# metrowing.net
KiCad netlist of a schematic drawn in EAGLE
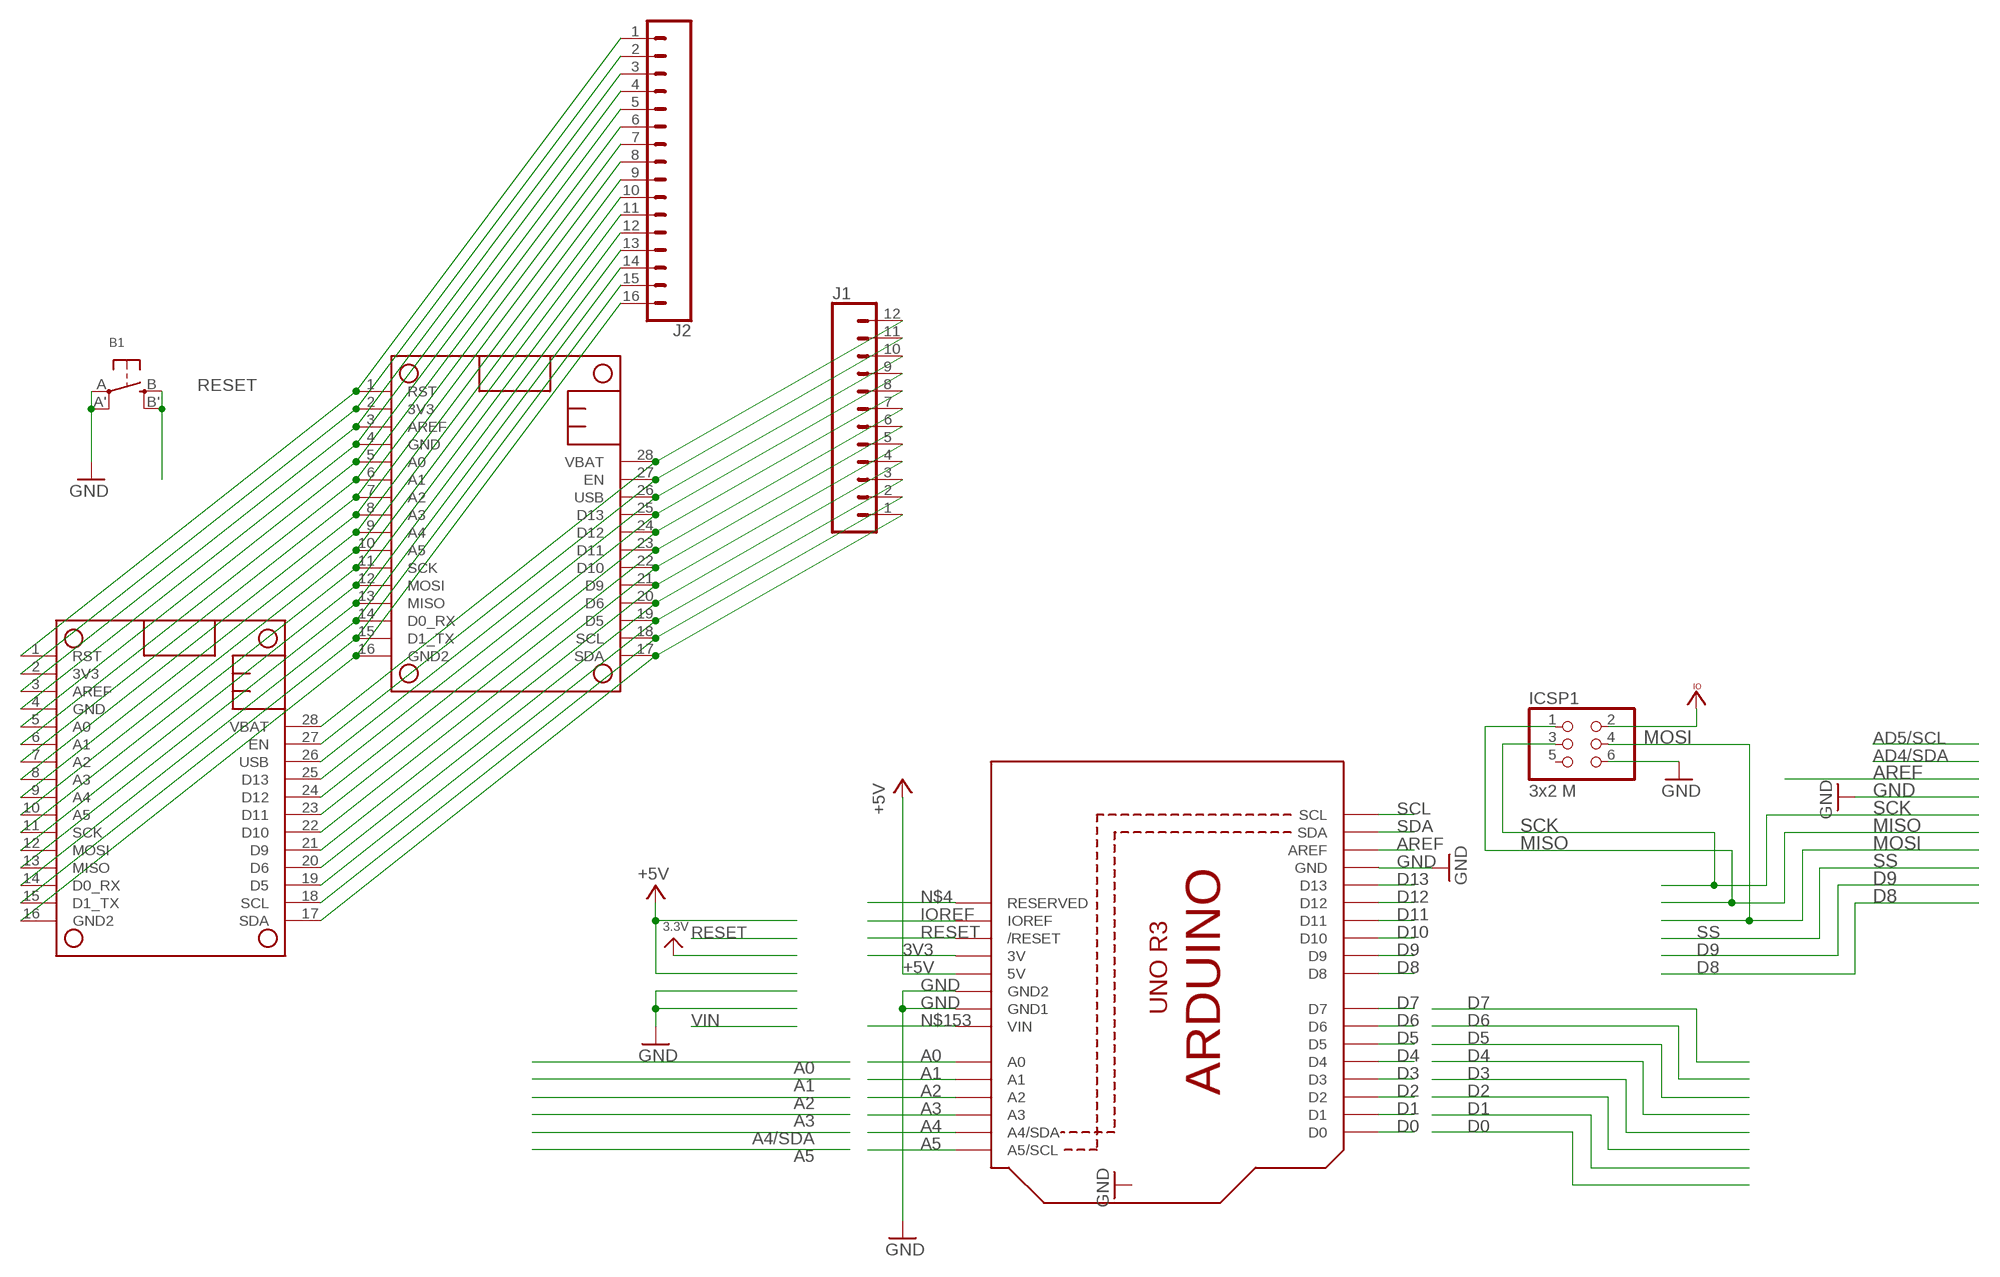
[diagram p0: schematic, sheet 1]

(export (version "E")
  (design (tool "Eeschema 10.0.6"))
  (components
    (comp (ref "B1")
      (value "SWITCH_TACT_SMT")
      (footprint "eagle-import:EVQ-Q2")
      (libsource (lib "eagle-import") (part "SWITCH_TACT_SMT"))
    )
    (comp (ref "ICSP1")
      (value "3x2 M")
      (footprint "eagle-import:2X03_ROUND_70MIL")
      (libsource (lib "eagle-import") (part "HEADER-2X3"))
    )
    (comp (ref "J1")
      (value "CONN_12")
      (footprint "eagle-import:1X12")
      (libsource (lib "eagle-import") (part "CONN_12"))
    )
    (comp (ref "J2")
      (value "CONN_16")
      (footprint "eagle-import:1X16")
      (libsource (lib "eagle-import") (part "CONN_16"))
    )
    (comp (ref "MS1")
      (value "FEATHERWING_PINS")
      (footprint "eagle-import:FEATHERWING_PINS")
      (libsource (lib "eagle-import") (part "FEATHERWING_PINS"))
    )
    (comp (ref "MS2")
      (value "FEATHERWING_PINS")
      (footprint "eagle-import:FEATHERWING_PINS")
      (libsource (lib "eagle-import") (part "FEATHERWING_PINS"))
    )
    (comp (ref "U1")
      (value "ARDUINOR3-DIMENSION")
      (footprint "eagle-import:ARDUINOR3")
      (libsource (lib "eagle-import") (part "ARDUINOR3-DIMENSION"))
    )
  )
  (nets
    (net (code "1") (name "+5V") (class "Default")
      (node (ref "J1") (pin "10") (pinfunction "10_10") (pintype "passive"))
      (node (ref "MS1") (pin "26") (pinfunction "USB_26") (pintype "power_in"))
      (node (ref "MS2") (pin "26") (pinfunction "USB_26") (pintype "power_in"))
      (node (ref "U1") (pin "5V") (pinfunction "5V_5V") (pintype "power_in"))
    )
    (net (code "2") (name "/3V3") (class "Default")
      (node (ref "J2") (pin "2") (pinfunction "2_2") (pintype "passive"))
      (node (ref "MS1") (pin "2") (pinfunction "3V3_2") (pintype "power_in"))
      (node (ref "MS2") (pin "2") (pinfunction "3V3_2") (pintype "power_in"))
      (node (ref "U1") (pin "3V") (pinfunction "3V_3V") (pintype "power_in"))
    )
    (net (code "3") (name "/A0") (class "Default")
      (node (ref "J2") (pin "5") (pinfunction "5_5") (pintype "passive"))
      (node (ref "MS1") (pin "5") (pinfunction "A0_5") (pintype "bidirectional"))
      (node (ref "MS2") (pin "5") (pinfunction "A0_5") (pintype "bidirectional"))
      (node (ref "U1") (pin "A0") (pinfunction "A0_A0") (pintype "bidirectional"))
    )
    (net (code "4") (name "/A1") (class "Default")
      (node (ref "J2") (pin "6") (pinfunction "6_6") (pintype "passive"))
      (node (ref "MS1") (pin "6") (pinfunction "A1_6") (pintype "bidirectional"))
      (node (ref "MS2") (pin "6") (pinfunction "A1_6") (pintype "bidirectional"))
      (node (ref "U1") (pin "A1") (pinfunction "A1_A1") (pintype "bidirectional"))
    )
    (net (code "5") (name "/A2") (class "Default")
      (node (ref "J2") (pin "7") (pinfunction "7_7") (pintype "passive"))
      (node (ref "MS1") (pin "7") (pinfunction "A2_7") (pintype "bidirectional"))
      (node (ref "MS2") (pin "7") (pinfunction "A2_7") (pintype "bidirectional"))
      (node (ref "U1") (pin "A2") (pinfunction "A2_A2") (pintype "bidirectional"))
    )
    (net (code "6") (name "/A3") (class "Default")
      (node (ref "J2") (pin "8") (pinfunction "8_8") (pintype "passive"))
      (node (ref "MS1") (pin "8") (pinfunction "A3_8") (pintype "bidirectional"))
      (node (ref "MS2") (pin "8") (pinfunction "A3_8") (pintype "bidirectional"))
      (node (ref "U1") (pin "A3") (pinfunction "A3_A3") (pintype "bidirectional"))
    )
    (net (code "7") (name "/A4") (class "Default")
      (node (ref "J2") (pin "9") (pinfunction "9_9") (pintype "passive"))
      (node (ref "MS1") (pin "9") (pinfunction "A4_9") (pintype "bidirectional"))
      (node (ref "MS2") (pin "9") (pinfunction "A4_9") (pintype "bidirectional"))
      (node (ref "U1") (pin "A4") (pinfunction "A4/SDA_A4") (pintype "bidirectional"))
    )
    (net (code "9") (name "/A5") (class "Default")
      (node (ref "J2") (pin "10") (pinfunction "10_10") (pintype "passive"))
      (node (ref "MS1") (pin "10") (pinfunction "A5_10") (pintype "bidirectional"))
      (node (ref "MS2") (pin "10") (pinfunction "A5_10") (pintype "bidirectional"))
      (node (ref "U1") (pin "A5") (pinfunction "A5/SCL_A5") (pintype "bidirectional"))
    )
    (net (code "12") (name "/AREF") (class "Default")
      (node (ref "J2") (pin "3") (pinfunction "3_3") (pintype "passive"))
      (node (ref "MS1") (pin "3") (pinfunction "AREF_3") (pintype "passive"))
      (node (ref "MS2") (pin "3") (pinfunction "AREF_3") (pintype "passive"))
      (node (ref "U1") (pin "AREF") (pinfunction "AREF_AREF") (pintype "bidirectional"))
    )
    (net (code "13") (name "/D0") (class "Default")
      (node (ref "J2") (pin "14") (pinfunction "14_14") (pintype "passive"))
      (node (ref "MS1") (pin "14") (pinfunction "D0_RX_14") (pintype "bidirectional"))
      (node (ref "MS2") (pin "14") (pinfunction "D0_RX_14") (pintype "bidirectional"))
      (node (ref "U1") (pin "D0") (pinfunction "D0_D0") (pintype "bidirectional"))
    )
    (net (code "14") (name "/D1") (class "Default")
      (node (ref "J2") (pin "15") (pinfunction "15_15") (pintype "passive"))
      (node (ref "MS1") (pin "15") (pinfunction "D1_TX_15") (pintype "bidirectional"))
      (node (ref "MS2") (pin "15") (pinfunction "D1_TX_15") (pintype "bidirectional"))
      (node (ref "U1") (pin "D1") (pinfunction "D1_D1") (pintype "bidirectional"))
    )
    (net (code "15") (name "/D2") (class "Default")
      (node (ref "U1") (pin "D2") (pinfunction "D2_D2") (pintype "bidirectional"))
    )
    (net (code "16") (name "/D3") (class "Default")
      (node (ref "U1") (pin "D3") (pinfunction "D3_D3") (pintype "bidirectional"))
    )
    (net (code "17") (name "/D4") (class "Default")
      (node (ref "U1") (pin "D4") (pinfunction "D4_D4") (pintype "bidirectional"))
    )
    (net (code "18") (name "/D5") (class "Default")
      (node (ref "J1") (pin "3") (pinfunction "3_3") (pintype "passive"))
      (node (ref "MS1") (pin "19") (pinfunction "D5_19") (pintype "bidirectional"))
      (node (ref "MS2") (pin "19") (pinfunction "D5_19") (pintype "bidirectional"))
      (node (ref "U1") (pin "D5") (pinfunction "D5_D5") (pintype "bidirectional"))
    )
    (net (code "19") (name "/D6") (class "Default")
      (node (ref "J1") (pin "4") (pinfunction "4_4") (pintype "passive"))
      (node (ref "MS1") (pin "20") (pinfunction "D6_20") (pintype "bidirectional"))
      (node (ref "MS2") (pin "20") (pinfunction "D6_20") (pintype "bidirectional"))
      (node (ref "U1") (pin "D6") (pinfunction "D6_D6") (pintype "bidirectional"))
    )
    (net (code "20") (name "/D7") (class "Default")
      (node (ref "U1") (pin "D7") (pinfunction "D7_D7") (pintype "bidirectional"))
    )
    (net (code "21") (name "/D8") (class "Default")
      (node (ref "U1") (pin "D8") (pinfunction "D8_D8") (pintype "bidirectional"))
    )
    (net (code "22") (name "/D9") (class "Default")
      (node (ref "J1") (pin "5") (pinfunction "5_5") (pintype "passive"))
      (node (ref "MS1") (pin "21") (pinfunction "D9_21") (pintype "bidirectional"))
      (node (ref "MS2") (pin "21") (pinfunction "D9_21") (pintype "bidirectional"))
      (node (ref "U1") (pin "D9") (pinfunction "D9_D9") (pintype "bidirectional"))
    )
    (net (code "23") (name "/D10") (class "Default")
      (node (ref "J1") (pin "6") (pinfunction "6_6") (pintype "passive"))
      (node (ref "MS1") (pin "22") (pinfunction "D10_22") (pintype "bidirectional"))
      (node (ref "MS2") (pin "22") (pinfunction "D10_22") (pintype "bidirectional"))
      (node (ref "U1") (pin "D10") (pinfunction "D10_D10") (pintype "bidirectional"))
    )
    (net (code "24") (name "/D11") (class "Default")
      (node (ref "J1") (pin "7") (pinfunction "7_7") (pintype "passive"))
      (node (ref "MS1") (pin "23") (pinfunction "D11_23") (pintype "bidirectional"))
      (node (ref "MS2") (pin "23") (pinfunction "D11_23") (pintype "bidirectional"))
      (node (ref "U1") (pin "D11") (pinfunction "D11_D11") (pintype "bidirectional"))
    )
    (net (code "25") (name "/D12") (class "Default")
      (node (ref "J1") (pin "8") (pinfunction "8_8") (pintype "passive"))
      (node (ref "MS1") (pin "24") (pinfunction "D12_24") (pintype "bidirectional"))
      (node (ref "MS2") (pin "24") (pinfunction "D12_24") (pintype "bidirectional"))
      (node (ref "U1") (pin "D12") (pinfunction "D12_D12") (pintype "bidirectional"))
    )
    (net (code "26") (name "/D13") (class "Default")
      (node (ref "J1") (pin "9") (pinfunction "9_9") (pintype "passive"))
      (node (ref "MS1") (pin "25") (pinfunction "D13_25") (pintype "bidirectional"))
      (node (ref "MS2") (pin "25") (pinfunction "D13_25") (pintype "bidirectional"))
      (node (ref "U1") (pin "D13") (pinfunction "D13_D13") (pintype "bidirectional"))
    )
    (net (code "27") (name "/IOREF") (class "Default")
      (node (ref "U1") (pin "IOREF") (pinfunction "IOREF_IOREF") (pintype "output"))
    )
    (net (code "28") (name "/MISO") (class "Default")
      (node (ref "ICSP1") (pin "1") (pinfunction "1_1") (pintype "passive"))
      (node (ref "J2") (pin "13") (pinfunction "13_13") (pintype "passive"))
      (node (ref "MS1") (pin "13") (pinfunction "MISO_13") (pintype "bidirectional"))
      (node (ref "MS2") (pin "13") (pinfunction "MISO_13") (pintype "bidirectional"))
    )
    (net (code "29") (name "/MOSI") (class "Default")
      (node (ref "ICSP1") (pin "4") (pinfunction "4_4") (pintype "passive"))
      (node (ref "J2") (pin "12") (pinfunction "12_12") (pintype "passive"))
      (node (ref "MS1") (pin "12") (pinfunction "MOSI_12") (pintype "bidirectional"))
      (node (ref "MS2") (pin "12") (pinfunction "MOSI_12") (pintype "bidirectional"))
    )
    (net (code "31") (name "/N$153") (class "Default")
      (node (ref "U1") (pin "VIN") (pinfunction "VIN_VIN") (pintype "power_in"))
    )
    (net (code "32") (name "/RESET") (class "Default")
      (node (ref "B1") (pin "B") (pinfunction "S_B") (pintype "passive"))
      (node (ref "B1") (pin "B'") (pinfunction "S1_B'") (pintype "passive"))
      (node (ref "J2") (pin "1") (pinfunction "1_1") (pintype "passive"))
      (node (ref "MS1") (pin "1") (pinfunction "RST_1") (pintype "input"))
      (node (ref "MS2") (pin "1") (pinfunction "RST_1") (pintype "input"))
      (node (ref "U1") (pin "RESET") (pinfunction "/RESET_RESET") (pintype "bidirectional"))
    )
    (net (code "33") (name "/SCK") (class "Default")
      (node (ref "ICSP1") (pin "3") (pinfunction "3_3") (pintype "passive"))
      (node (ref "J2") (pin "11") (pinfunction "11_11") (pintype "passive"))
      (node (ref "MS1") (pin "11") (pinfunction "SCK_11") (pintype "bidirectional"))
      (node (ref "MS2") (pin "11") (pinfunction "SCK_11") (pintype "bidirectional"))
    )
    (net (code "34") (name "/SCL") (class "Default")
      (node (ref "J1") (pin "2") (pinfunction "2_2") (pintype "passive"))
      (node (ref "MS1") (pin "18") (pinfunction "SCL_18") (pintype "bidirectional"))
      (node (ref "MS2") (pin "18") (pinfunction "SCL_18") (pintype "bidirectional"))
      (node (ref "U1") (pin "SCL") (pinfunction "SCL_SCL") (pintype "bidirectional"))
    )
    (net (code "35") (name "/SDA") (class "Default")
      (node (ref "J1") (pin "1") (pinfunction "1_1") (pintype "passive"))
      (node (ref "MS1") (pin "17") (pinfunction "SDA_17") (pintype "bidirectional"))
      (node (ref "MS2") (pin "17") (pinfunction "SDA_17") (pintype "bidirectional"))
      (node (ref "U1") (pin "SDA") (pinfunction "SDA_SDA") (pintype "bidirectional"))
    )
    (net (code "39") (name "GND") (class "Default")
      (node (ref "B1") (pin "A") (pinfunction "P_A") (pintype "passive"))
      (node (ref "B1") (pin "A'") (pinfunction "P1_A'") (pintype "passive"))
      (node (ref "ICSP1") (pin "6") (pinfunction "6_6") (pintype "passive"))
      (node (ref "J2") (pin "16") (pinfunction "16_16") (pintype "passive"))
      (node (ref "J2") (pin "4") (pinfunction "4_4") (pintype "passive"))
      (node (ref "MS1") (pin "16") (pinfunction "GND2_16") (pintype "passive"))
      (node (ref "MS1") (pin "4") (pinfunction "GND_4") (pintype "power_in"))
      (node (ref "MS2") (pin "16") (pinfunction "GND2_16") (pintype "passive"))
      (node (ref "MS2") (pin "4") (pinfunction "GND_4") (pintype "power_in"))
      (node (ref "U1") (pin "GND") (pinfunction "GND_GND") (pintype "power_in"))
      (node (ref "U1") (pin "GND1") (pinfunction "GND1_GND1") (pintype "power_in"))
      (node (ref "U1") (pin "GND2") (pinfunction "GND2_GND2") (pintype "power_in"))
    )
    (net (code "40") (name "Net-(MS1-EN)") (class "Default")
      (node (ref "J1") (pin "11") (pinfunction "11_11") (pintype "passive"))
      (node (ref "MS1") (pin "27") (pinfunction "EN_27") (pintype "passive"))
      (node (ref "MS2") (pin "27") (pinfunction "EN_27") (pintype "passive"))
    )
    (net (code "41") (name "Net-(MS1-VBAT)") (class "Default")
      (node (ref "J1") (pin "12") (pinfunction "12_12") (pintype "passive"))
      (node (ref "MS1") (pin "28") (pinfunction "VBAT_28") (pintype "power_in"))
      (node (ref "MS2") (pin "28") (pinfunction "VBAT_28") (pintype "power_in"))
    )
    (net (code "42") (name "VCCIO") (class "Default")
      (node (ref "ICSP1") (pin "2") (pinfunction "2_2") (pintype "passive"))
    )
    (net (code "43") (name "unconnected-(ICSP1-Pad5)") (class "Default")
      (node (ref "ICSP1") (pin "5") (pinfunction "5_5") (pintype "passive"))
    )
    (net (code "44") (name "unconnected-(U1-PadRESERVED)") (class "Default")
      (node (ref "U1") (pin "RESERVED") (pinfunction "RESERVED_RESERVED") (pintype "no_connect"))
    )
  )
)
